# SENSOR_SCH_HDMI.net
KiCad netlist of a schematic drawn in EasyEDA
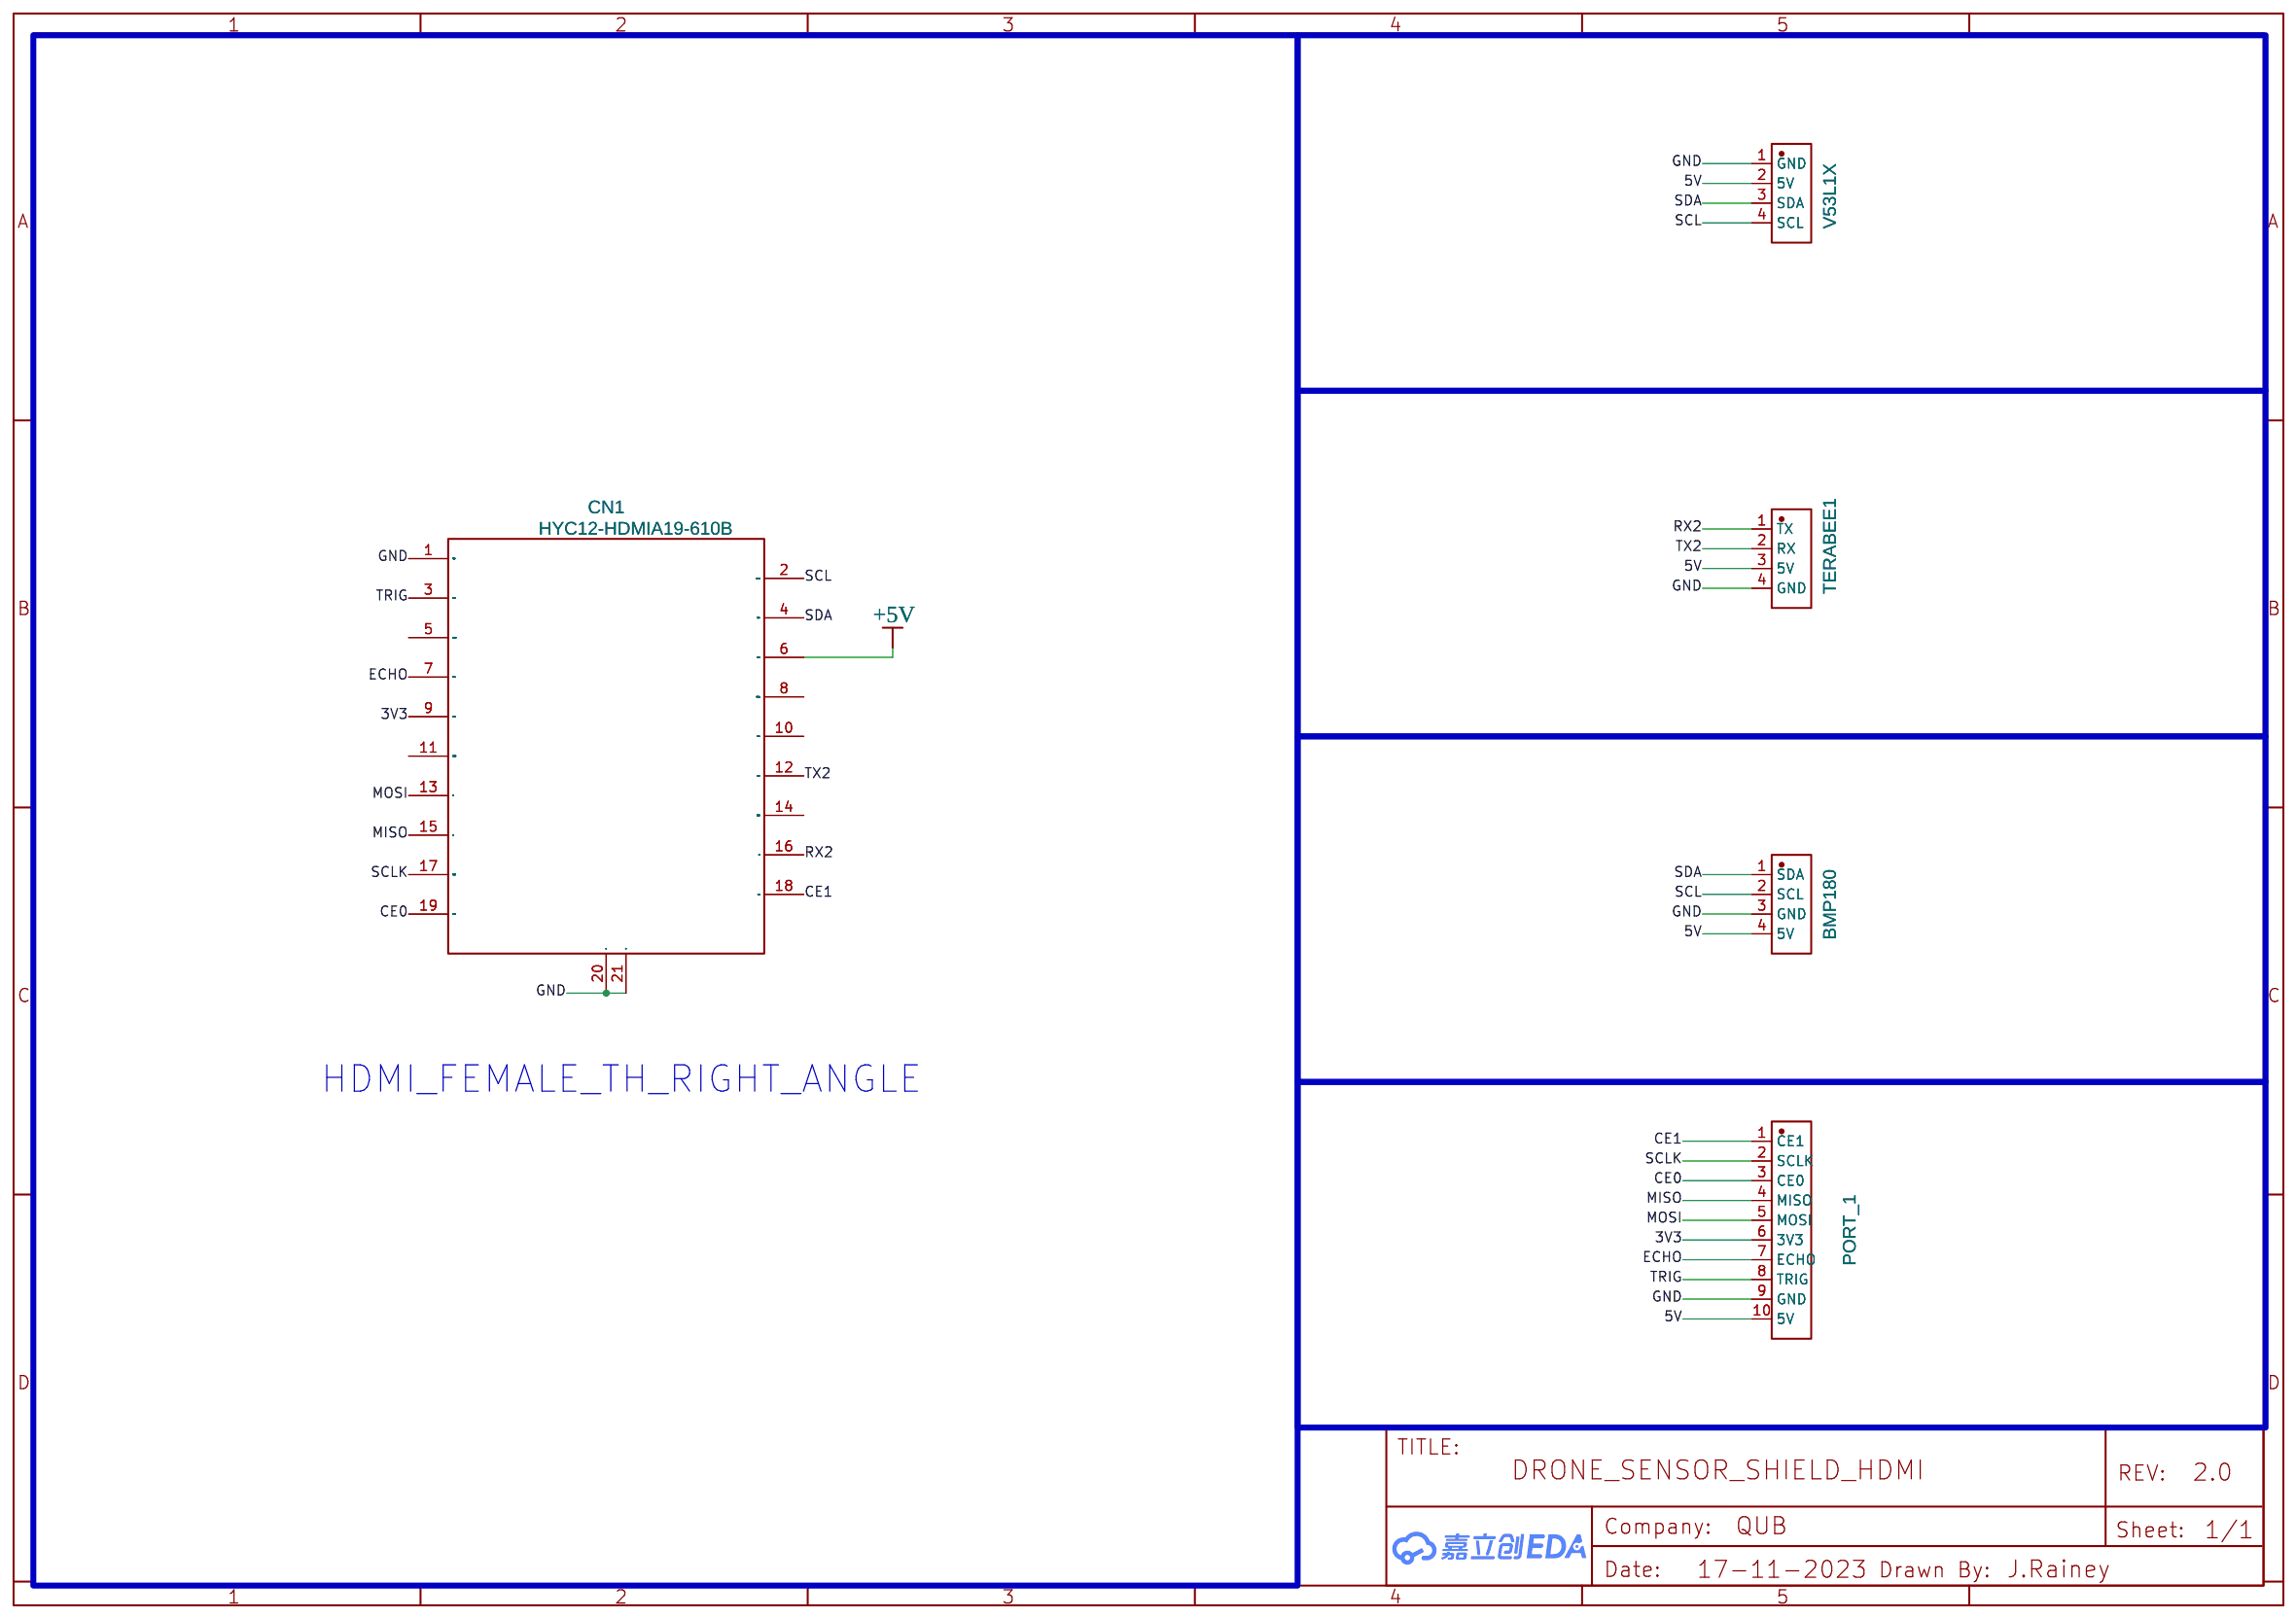
[diagram p0: schematic sheet]

(export (version "E")
  (design (tool "Eeschema 10.0.6"))
  (components
    (comp (ref "BMP180")
      (value "PZ254V-11-04P")
      (fields (field (name "BOM_Supplier Part") "C492403"))
      (libsource (lib "") (part "PZ254V-11-04P"))
    )
    (comp (ref "CN1")
      (value "HYC12-HDMIA19-610B")
      (fields (field (name "BOM_Supplier Part") "C711354"))
      (libsource (lib "") (part "HYC12-HDMIA19-610B"))
    )
    (comp (ref "PORT_1")
      (value "PORT_1")
      (fields (field (name "Manufacturer Part") "cn10_2r54_10x1"))
      (libsource (lib "") (part "CN10_2R54_10X1"))
    )
    (comp (ref "TERABEE1")
      (value "PZ254V-11-04P")
      (fields (field (name "BOM_Supplier Part") "C492403"))
      (libsource (lib "") (part "PZ254V-11-04P_1"))
    )
    (comp (ref "V53L1X")
      (value "PZ254V-11-04P")
      (fields (field (name "BOM_Supplier Part") "C492403"))
      (libsource (lib "") (part "PZ254V-11-04P_2"))
    )
  )
  (nets
    (net (code "1") (name "+5V") (class "Default")
      (node (ref "CN1") (pin "6") (pinfunction "TMDS_Data_1-_6") (pintype "unspecified"))
    )
    (net (code "2") (name "/3V3") (class "Default")
      (node (ref "CN1") (pin "9") (pinfunction "TMDS_Data_0-_9") (pintype "unspecified"))
      (node (ref "PORT_1") (pin "6") (pinfunction "3V3_6") (pintype "unspecified"))
    )
    (net (code "3") (name "/5V") (class "Default")
      (node (ref "BMP180") (pin "4") (pinfunction "5V_4") (pintype "unspecified"))
      (node (ref "PORT_1") (pin "10") (pinfunction "5V_10") (pintype "unspecified"))
      (node (ref "TERABEE1") (pin "3") (pinfunction "5V_3") (pintype "unspecified"))
      (node (ref "V53L1X") (pin "2") (pinfunction "5V_2") (pintype "unspecified"))
    )
    (net (code "4") (name "/CE0") (class "Default")
      (node (ref "CN1") (pin "19") (pinfunction "Hot_Plug_Detect_19") (pintype "unspecified"))
      (node (ref "PORT_1") (pin "3") (pinfunction "CE0_3") (pintype "unspecified"))
    )
    (net (code "5") (name "/CE1") (class "Default")
      (node (ref "CN1") (pin "18") (pinfunction "+5V_Power_18") (pintype "unspecified"))
      (node (ref "PORT_1") (pin "1") (pinfunction "CE1_1") (pintype "unspecified"))
    )
    (net (code "6") (name "/ECHO") (class "Default")
      (node (ref "CN1") (pin "7") (pinfunction "TMDS_Data_0+_7") (pintype "unspecified"))
      (node (ref "PORT_1") (pin "7") (pinfunction "ECHO_7") (pintype "unspecified"))
    )
    (net (code "7") (name "/GND") (class "Default")
      (node (ref "BMP180") (pin "3") (pinfunction "GND_3") (pintype "unspecified"))
      (node (ref "CN1") (pin "1") (pinfunction "TMDS_Data_2+_1") (pintype "unspecified"))
      (node (ref "CN1") (pin "20") (pinfunction "EH_20") (pintype "unspecified"))
      (node (ref "CN1") (pin "21") (pinfunction "EH_21") (pintype "unspecified"))
      (node (ref "PORT_1") (pin "9") (pinfunction "GND_9") (pintype "unspecified"))
      (node (ref "TERABEE1") (pin "4") (pinfunction "GND_4") (pintype "unspecified"))
      (node (ref "V53L1X") (pin "1") (pinfunction "GND_1") (pintype "unspecified"))
    )
    (net (code "8") (name "/MISO") (class "Default")
      (node (ref "CN1") (pin "15") (pinfunction "SCL_15") (pintype "unspecified"))
      (node (ref "PORT_1") (pin "4") (pinfunction "MISO_4") (pintype "unspecified"))
    )
    (net (code "9") (name "/MOSI") (class "Default")
      (node (ref "CN1") (pin "13") (pinfunction "CEC_13") (pintype "unspecified"))
      (node (ref "PORT_1") (pin "5") (pinfunction "MOSI_5") (pintype "unspecified"))
    )
    (net (code "10") (name "/RX2") (class "Default")
      (node (ref "CN1") (pin "16") (pinfunction "SDA_16") (pintype "unspecified"))
      (node (ref "TERABEE1") (pin "1") (pinfunction "TX_1") (pintype "unspecified"))
    )
    (net (code "11") (name "/SCL") (class "Default")
      (node (ref "BMP180") (pin "2") (pinfunction "SCL_2") (pintype "unspecified"))
      (node (ref "CN1") (pin "2") (pinfunction "TMDS_Data_2_Shield_2") (pintype "unspecified"))
      (node (ref "V53L1X") (pin "4") (pinfunction "SCL_4") (pintype "unspecified"))
    )
    (net (code "12") (name "/SCLK") (class "Default")
      (node (ref "CN1") (pin "17") (pinfunction "DDC/CEC_Ground_17") (pintype "unspecified"))
      (node (ref "PORT_1") (pin "2") (pinfunction "SCLK_2") (pintype "unspecified"))
    )
    (net (code "13") (name "/SDA") (class "Default")
      (node (ref "BMP180") (pin "1") (pinfunction "SDA_1") (pintype "unspecified"))
      (node (ref "CN1") (pin "4") (pinfunction "TMDS_Data_1+_4") (pintype "unspecified"))
      (node (ref "V53L1X") (pin "3") (pinfunction "SDA_3") (pintype "unspecified"))
    )
    (net (code "14") (name "/TRIG") (class "Default")
      (node (ref "CN1") (pin "3") (pinfunction "TMDS_Data_2-_3") (pintype "unspecified"))
      (node (ref "PORT_1") (pin "8") (pinfunction "TRIG_8") (pintype "unspecified"))
    )
    (net (code "15") (name "/TX2") (class "Default")
      (node (ref "CN1") (pin "12") (pinfunction "TMDS_Clock-_12") (pintype "unspecified"))
      (node (ref "TERABEE1") (pin "2") (pinfunction "RX_2") (pintype "unspecified"))
    )
    (net (code "16") (name "unconnected-(CN1-Reserved_(N.C.)-Pad14)") (class "Default")
      (node (ref "CN1") (pin "14") (pinfunction "Reserved_(N.C.)_14") (pintype "unspecified"))
    )
    (net (code "17") (name "unconnected-(CN1-TMDS_Clock+-Pad10)") (class "Default")
      (node (ref "CN1") (pin "10") (pinfunction "TMDS_Clock+_10") (pintype "unspecified"))
    )
    (net (code "18") (name "unconnected-(CN1-TMDS_Clock_Shield-Pad11)") (class "Default")
      (node (ref "CN1") (pin "11") (pinfunction "TMDS_Clock_Shield_11") (pintype "unspecified"))
    )
    (net (code "19") (name "unconnected-(CN1-TMDS_Data_0_Shield-Pad8)") (class "Default")
      (node (ref "CN1") (pin "8") (pinfunction "TMDS_Data_0_Shield_8") (pintype "unspecified"))
    )
    (net (code "20") (name "unconnected-(CN1-TMDS_Data_1_Shield-Pad5)") (class "Default")
      (node (ref "CN1") (pin "5") (pinfunction "TMDS_Data_1_Shield_5") (pintype "unspecified"))
    )
  )
)
